# Maxim_7219_LED_display_KingBright_7_segm.net
KiCad netlist of a schematic drawn in EAGLE
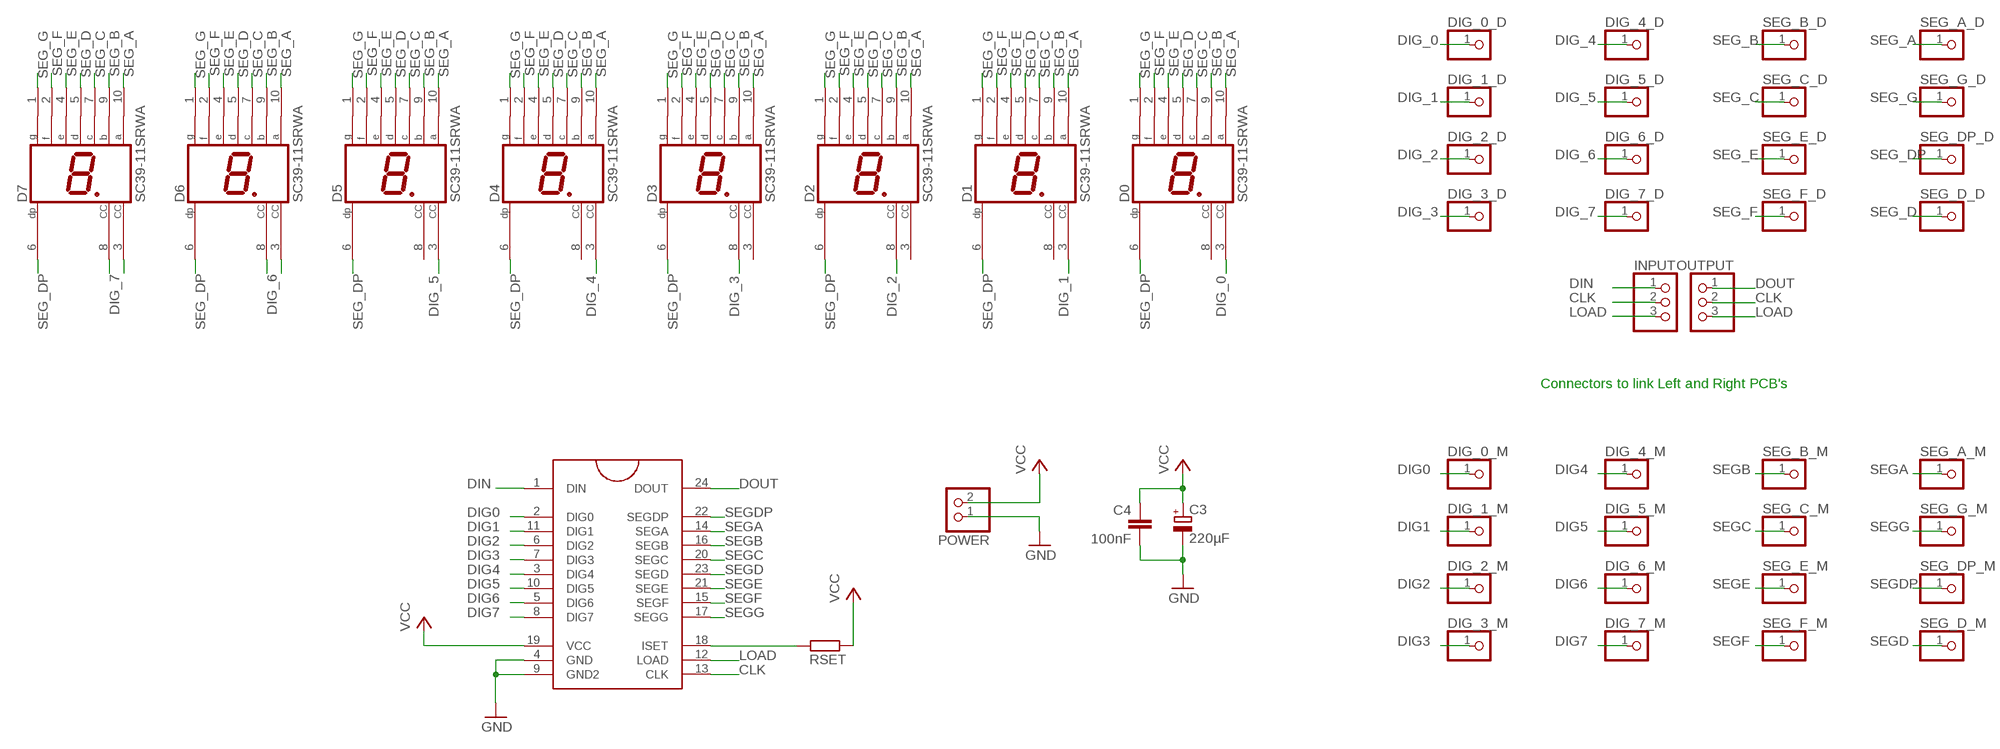
[diagram p0: schematic, sheet 1]

(export (version "E")
  (design (tool "Eeschema 10.0.6"))
  (components
    (comp (ref "C3")
      (value "220µF")
      (footprint "eagle-import:E3,5-8")
      (libsource (lib "eagle-import") (part "CPOL-EUE3.5-8"))
    )
    (comp (ref "C4")
      (value "100nF")
      (footprint "eagle-import:C050-025X075")
      (libsource (lib "eagle-import") (part "C-EU050-025X075"))
    )
    (comp (ref "D0")
      (value "SC39-11SRWA")
      (footprint "eagle-import:HDSP-E")
      (libsource (lib "eagle-import") (part "SC39-11SRWA"))
    )
    (comp (ref "D1")
      (value "SC39-11SRWA")
      (footprint "eagle-import:HDSP-E")
      (libsource (lib "eagle-import") (part "SC39-11SRWA"))
    )
    (comp (ref "D2")
      (value "SC39-11SRWA")
      (footprint "eagle-import:HDSP-E")
      (libsource (lib "eagle-import") (part "SC39-11SRWA"))
    )
    (comp (ref "D3")
      (value "SC39-11SRWA")
      (footprint "eagle-import:HDSP-E")
      (libsource (lib "eagle-import") (part "SC39-11SRWA"))
    )
    (comp (ref "D4")
      (value "SC39-11SRWA")
      (footprint "eagle-import:HDSP-E")
      (libsource (lib "eagle-import") (part "SC39-11SRWA"))
    )
    (comp (ref "D5")
      (value "SC39-11SRWA")
      (footprint "eagle-import:HDSP-E")
      (libsource (lib "eagle-import") (part "SC39-11SRWA"))
    )
    (comp (ref "D6")
      (value "SC39-11SRWA")
      (footprint "eagle-import:HDSP-E")
      (libsource (lib "eagle-import") (part "SC39-11SRWA"))
    )
    (comp (ref "D7")
      (value "SC39-11SRWA")
      (footprint "eagle-import:HDSP-E")
      (libsource (lib "eagle-import") (part "SC39-11SRWA"))
    )
    (comp (ref "DIG_0_D")
      (value "PINHD-1X1")
      (footprint "eagle-import:1X01")
      (libsource (lib "eagle-import") (part "PINHD-1X1"))
    )
    (comp (ref "DIG_0_M")
      (value "PINHD-1X1")
      (footprint "eagle-import:1X01")
      (libsource (lib "eagle-import") (part "PINHD-1X1"))
    )
    (comp (ref "DIG_1_D")
      (value "PINHD-1X1")
      (footprint "eagle-import:1X01")
      (libsource (lib "eagle-import") (part "PINHD-1X1"))
    )
    (comp (ref "DIG_1_M")
      (value "PINHD-1X1")
      (footprint "eagle-import:1X01")
      (libsource (lib "eagle-import") (part "PINHD-1X1"))
    )
    (comp (ref "DIG_2_D")
      (value "PINHD-1X1")
      (footprint "eagle-import:1X01")
      (libsource (lib "eagle-import") (part "PINHD-1X1"))
    )
    (comp (ref "DIG_2_M")
      (value "PINHD-1X1")
      (footprint "eagle-import:1X01")
      (libsource (lib "eagle-import") (part "PINHD-1X1"))
    )
    (comp (ref "DIG_3_D")
      (value "PINHD-1X1")
      (footprint "eagle-import:1X01")
      (libsource (lib "eagle-import") (part "PINHD-1X1"))
    )
    (comp (ref "DIG_3_M")
      (value "PINHD-1X1")
      (footprint "eagle-import:1X01")
      (libsource (lib "eagle-import") (part "PINHD-1X1"))
    )
    (comp (ref "DIG_4_D")
      (value "PINHD-1X1")
      (footprint "eagle-import:1X01")
      (libsource (lib "eagle-import") (part "PINHD-1X1"))
    )
    (comp (ref "DIG_4_M")
      (value "PINHD-1X1")
      (footprint "eagle-import:1X01")
      (libsource (lib "eagle-import") (part "PINHD-1X1"))
    )
    (comp (ref "DIG_5_D")
      (value "PINHD-1X1")
      (footprint "eagle-import:1X01")
      (libsource (lib "eagle-import") (part "PINHD-1X1"))
    )
    (comp (ref "DIG_5_M")
      (value "PINHD-1X1")
      (footprint "eagle-import:1X01")
      (libsource (lib "eagle-import") (part "PINHD-1X1"))
    )
    (comp (ref "DIG_6_D")
      (value "PINHD-1X1")
      (footprint "eagle-import:1X01")
      (libsource (lib "eagle-import") (part "PINHD-1X1"))
    )
    (comp (ref "DIG_6_M")
      (value "PINHD-1X1")
      (footprint "eagle-import:1X01")
      (libsource (lib "eagle-import") (part "PINHD-1X1"))
    )
    (comp (ref "DIG_7_D")
      (value "PINHD-1X1")
      (footprint "eagle-import:1X01")
      (libsource (lib "eagle-import") (part "PINHD-1X1"))
    )
    (comp (ref "DIG_7_M")
      (value "PINHD-1X1")
      (footprint "eagle-import:1X01")
      (libsource (lib "eagle-import") (part "PINHD-1X1"))
    )
    (comp (ref "INPUT")
      (value "PINHD-1X3")
      (footprint "eagle-import:1X03")
      (libsource (lib "eagle-import") (part "PINHD-1X3"))
    )
    (comp (ref "OUTPUT")
      (value "PINHD-1X3")
      (footprint "eagle-import:1X03")
      (libsource (lib "eagle-import") (part "PINHD-1X3"))
    )
    (comp (ref "POWER")
      (value "PINHD-1X2")
      (footprint "eagle-import:1X02")
      (libsource (lib "eagle-import") (part "PINHD-1X2"))
    )
    (comp (ref "RSET")
      (value "R-EU_0207/10")
      (footprint "eagle-import:0207_10")
      (libsource (lib "eagle-import") (part "R-EU_0207/10"))
    )
    (comp (ref "SEG_A_D")
      (value "PINHD-1X1")
      (footprint "eagle-import:1X01")
      (libsource (lib "eagle-import") (part "PINHD-1X1"))
    )
    (comp (ref "SEG_A_M")
      (value "PINHD-1X1")
      (footprint "eagle-import:1X01")
      (libsource (lib "eagle-import") (part "PINHD-1X1"))
    )
    (comp (ref "SEG_B_D")
      (value "PINHD-1X1")
      (footprint "eagle-import:1X01")
      (libsource (lib "eagle-import") (part "PINHD-1X1"))
    )
    (comp (ref "SEG_B_M")
      (value "PINHD-1X1")
      (footprint "eagle-import:1X01")
      (libsource (lib "eagle-import") (part "PINHD-1X1"))
    )
    (comp (ref "SEG_C_D")
      (value "PINHD-1X1")
      (footprint "eagle-import:1X01")
      (libsource (lib "eagle-import") (part "PINHD-1X1"))
    )
    (comp (ref "SEG_C_M")
      (value "PINHD-1X1")
      (footprint "eagle-import:1X01")
      (libsource (lib "eagle-import") (part "PINHD-1X1"))
    )
    (comp (ref "SEG_DP_D")
      (value "PINHD-1X1")
      (footprint "eagle-import:1X01")
      (libsource (lib "eagle-import") (part "PINHD-1X1"))
    )
    (comp (ref "SEG_DP_M")
      (value "PINHD-1X1")
      (footprint "eagle-import:1X01")
      (libsource (lib "eagle-import") (part "PINHD-1X1"))
    )
    (comp (ref "SEG_D_D")
      (value "PINHD-1X1")
      (footprint "eagle-import:1X01")
      (libsource (lib "eagle-import") (part "PINHD-1X1"))
    )
    (comp (ref "SEG_D_M")
      (value "PINHD-1X1")
      (footprint "eagle-import:1X01")
      (libsource (lib "eagle-import") (part "PINHD-1X1"))
    )
    (comp (ref "SEG_E_D")
      (value "PINHD-1X1")
      (footprint "eagle-import:1X01")
      (libsource (lib "eagle-import") (part "PINHD-1X1"))
    )
    (comp (ref "SEG_E_M")
      (value "PINHD-1X1")
      (footprint "eagle-import:1X01")
      (libsource (lib "eagle-import") (part "PINHD-1X1"))
    )
    (comp (ref "SEG_F_D")
      (value "PINHD-1X1")
      (footprint "eagle-import:1X01")
      (libsource (lib "eagle-import") (part "PINHD-1X1"))
    )
    (comp (ref "SEG_F_M")
      (value "PINHD-1X1")
      (footprint "eagle-import:1X01")
      (libsource (lib "eagle-import") (part "PINHD-1X1"))
    )
    (comp (ref "SEG_G_D")
      (value "PINHD-1X1")
      (footprint "eagle-import:1X01")
      (libsource (lib "eagle-import") (part "PINHD-1X1"))
    )
    (comp (ref "SEG_G_M")
      (value "PINHD-1X1")
      (footprint "eagle-import:1X01")
      (libsource (lib "eagle-import") (part "PINHD-1X1"))
    )
    (comp (ref "U$3")
      (value "MAX7219DIP")
      (footprint "eagle-import:DIL24")
      (libsource (lib "eagle-import") (part "MAX7219DIP"))
    )
  )
  (nets
    (net (code "1") (name "/CLK") (class "Default")
      (node (ref "INPUT") (pin "2") (pinfunction "2_2") (pintype "passive"))
      (node (ref "OUTPUT") (pin "2") (pinfunction "2_2") (pintype "passive"))
      (node (ref "U$3") (pin "13") (pinfunction "CLK_13") (pintype "bidirectional"))
    )
    (net (code "2") (name "/DIG0") (class "Default")
      (node (ref "DIG_0_M") (pin "1") (pinfunction "1_1") (pintype "passive"))
      (node (ref "U$3") (pin "2") (pinfunction "DIG0_2") (pintype "bidirectional"))
    )
    (net (code "3") (name "/DIG1") (class "Default")
      (node (ref "DIG_1_M") (pin "1") (pinfunction "1_1") (pintype "passive"))
      (node (ref "U$3") (pin "11") (pinfunction "DIG1_11") (pintype "bidirectional"))
    )
    (net (code "4") (name "/DIG2") (class "Default")
      (node (ref "DIG_2_M") (pin "1") (pinfunction "1_1") (pintype "passive"))
      (node (ref "U$3") (pin "6") (pinfunction "DIG2_6") (pintype "bidirectional"))
    )
    (net (code "5") (name "/DIG3") (class "Default")
      (node (ref "DIG_3_M") (pin "1") (pinfunction "1_1") (pintype "passive"))
      (node (ref "U$3") (pin "7") (pinfunction "DIG3_7") (pintype "bidirectional"))
    )
    (net (code "6") (name "/DIG4") (class "Default")
      (node (ref "DIG_4_M") (pin "1") (pinfunction "1_1") (pintype "passive"))
      (node (ref "U$3") (pin "3") (pinfunction "DIG4_3") (pintype "bidirectional"))
    )
    (net (code "7") (name "/DIG5") (class "Default")
      (node (ref "DIG_5_M") (pin "1") (pinfunction "1_1") (pintype "passive"))
      (node (ref "U$3") (pin "10") (pinfunction "DIG5_10") (pintype "bidirectional"))
    )
    (net (code "8") (name "/DIG6") (class "Default")
      (node (ref "DIG_6_M") (pin "1") (pinfunction "1_1") (pintype "passive"))
      (node (ref "U$3") (pin "5") (pinfunction "DIG6_5") (pintype "bidirectional"))
    )
    (net (code "9") (name "/DIG7") (class "Default")
      (node (ref "DIG_7_M") (pin "1") (pinfunction "1_1") (pintype "passive"))
      (node (ref "U$3") (pin "8") (pinfunction "DIG7_8") (pintype "bidirectional"))
    )
    (net (code "10") (name "/DIG_0") (class "Default")
      (node (ref "D0") (pin "3") (pinfunction "CC_3") (pintype "passive"))
      (node (ref "DIG_0_D") (pin "1") (pinfunction "1_1") (pintype "passive"))
    )
    (net (code "11") (name "/DIG_1") (class "Default")
      (node (ref "D1") (pin "3") (pinfunction "CC_3") (pintype "passive"))
      (node (ref "DIG_1_D") (pin "1") (pinfunction "1_1") (pintype "passive"))
    )
    (net (code "12") (name "/DIG_2") (class "Default")
      (node (ref "D2") (pin "8") (pinfunction "CC_8") (pintype "passive"))
      (node (ref "DIG_2_D") (pin "1") (pinfunction "1_1") (pintype "passive"))
    )
    (net (code "13") (name "/DIG_3") (class "Default")
      (node (ref "D3") (pin "8") (pinfunction "CC_8") (pintype "passive"))
      (node (ref "DIG_3_D") (pin "1") (pinfunction "1_1") (pintype "passive"))
    )
    (net (code "14") (name "/DIG_4") (class "Default")
      (node (ref "D4") (pin "3") (pinfunction "CC_3") (pintype "passive"))
      (node (ref "DIG_4_D") (pin "1") (pinfunction "1_1") (pintype "passive"))
    )
    (net (code "15") (name "/DIG_5") (class "Default")
      (node (ref "D5") (pin "3") (pinfunction "CC_3") (pintype "passive"))
      (node (ref "DIG_5_D") (pin "1") (pinfunction "1_1") (pintype "passive"))
    )
    (net (code "16") (name "/DIG_6") (class "Default")
      (node (ref "D6") (pin "8") (pinfunction "CC_8") (pintype "passive"))
      (node (ref "DIG_6_D") (pin "1") (pinfunction "1_1") (pintype "passive"))
    )
    (net (code "17") (name "/DIG_7") (class "Default")
      (node (ref "D7") (pin "8") (pinfunction "CC_8") (pintype "passive"))
      (node (ref "DIG_7_D") (pin "1") (pinfunction "1_1") (pintype "passive"))
    )
    (net (code "18") (name "/DIN") (class "Default")
      (node (ref "INPUT") (pin "1") (pinfunction "1_1") (pintype "passive"))
      (node (ref "U$3") (pin "1") (pinfunction "DIN_1") (pintype "bidirectional"))
    )
    (net (code "19") (name "/DOUT") (class "Default")
      (node (ref "OUTPUT") (pin "1") (pinfunction "1_1") (pintype "passive"))
      (node (ref "U$3") (pin "24") (pinfunction "DOUT_24") (pintype "bidirectional"))
    )
    (net (code "20") (name "/LOAD") (class "Default")
      (node (ref "INPUT") (pin "3") (pinfunction "3_3") (pintype "passive"))
      (node (ref "OUTPUT") (pin "3") (pinfunction "3_3") (pintype "passive"))
      (node (ref "U$3") (pin "12") (pinfunction "LOAD_12") (pintype "bidirectional"))
    )
    (net (code "21") (name "/SEGA") (class "Default")
      (node (ref "SEG_A_M") (pin "1") (pinfunction "1_1") (pintype "passive"))
      (node (ref "U$3") (pin "14") (pinfunction "SEGA_14") (pintype "bidirectional"))
    )
    (net (code "22") (name "/SEGB") (class "Default")
      (node (ref "SEG_B_M") (pin "1") (pinfunction "1_1") (pintype "passive"))
      (node (ref "U$3") (pin "16") (pinfunction "SEGB_16") (pintype "bidirectional"))
    )
    (net (code "23") (name "/SEGC") (class "Default")
      (node (ref "SEG_C_M") (pin "1") (pinfunction "1_1") (pintype "passive"))
      (node (ref "U$3") (pin "20") (pinfunction "SEGC_20") (pintype "bidirectional"))
    )
    (net (code "24") (name "/SEGD") (class "Default")
      (node (ref "SEG_D_M") (pin "1") (pinfunction "1_1") (pintype "passive"))
      (node (ref "U$3") (pin "23") (pinfunction "SEGD_23") (pintype "bidirectional"))
    )
    (net (code "25") (name "/SEGDP") (class "Default")
      (node (ref "SEG_DP_M") (pin "1") (pinfunction "1_1") (pintype "passive"))
      (node (ref "U$3") (pin "22") (pinfunction "SEGDP_22") (pintype "bidirectional"))
    )
    (net (code "26") (name "/SEGE") (class "Default")
      (node (ref "SEG_E_M") (pin "1") (pinfunction "1_1") (pintype "passive"))
      (node (ref "U$3") (pin "21") (pinfunction "SEGE_21") (pintype "bidirectional"))
    )
    (net (code "27") (name "/SEGF") (class "Default")
      (node (ref "SEG_F_M") (pin "1") (pinfunction "1_1") (pintype "passive"))
      (node (ref "U$3") (pin "15") (pinfunction "SEGF_15") (pintype "bidirectional"))
    )
    (net (code "28") (name "/SEGG") (class "Default")
      (node (ref "SEG_G_M") (pin "1") (pinfunction "1_1") (pintype "passive"))
      (node (ref "U$3") (pin "17") (pinfunction "SEGG_17") (pintype "bidirectional"))
    )
    (net (code "29") (name "/SEG_A") (class "Default")
      (node (ref "D0") (pin "10") (pinfunction "A_10") (pintype "passive"))
      (node (ref "D1") (pin "10") (pinfunction "A_10") (pintype "passive"))
      (node (ref "D2") (pin "10") (pinfunction "A_10") (pintype "passive"))
      (node (ref "D3") (pin "10") (pinfunction "A_10") (pintype "passive"))
      (node (ref "D4") (pin "10") (pinfunction "A_10") (pintype "passive"))
      (node (ref "D5") (pin "10") (pinfunction "A_10") (pintype "passive"))
      (node (ref "D6") (pin "10") (pinfunction "A_10") (pintype "passive"))
      (node (ref "D7") (pin "10") (pinfunction "A_10") (pintype "passive"))
      (node (ref "SEG_A_D") (pin "1") (pinfunction "1_1") (pintype "passive"))
    )
    (net (code "30") (name "/SEG_B") (class "Default")
      (node (ref "D0") (pin "9") (pinfunction "B_9") (pintype "passive"))
      (node (ref "D1") (pin "9") (pinfunction "B_9") (pintype "passive"))
      (node (ref "D2") (pin "9") (pinfunction "B_9") (pintype "passive"))
      (node (ref "D3") (pin "9") (pinfunction "B_9") (pintype "passive"))
      (node (ref "D4") (pin "9") (pinfunction "B_9") (pintype "passive"))
      (node (ref "D5") (pin "9") (pinfunction "B_9") (pintype "passive"))
      (node (ref "D6") (pin "9") (pinfunction "B_9") (pintype "passive"))
      (node (ref "D7") (pin "9") (pinfunction "B_9") (pintype "passive"))
      (node (ref "SEG_B_D") (pin "1") (pinfunction "1_1") (pintype "passive"))
    )
    (net (code "31") (name "/SEG_C") (class "Default")
      (node (ref "D0") (pin "7") (pinfunction "C_7") (pintype "passive"))
      (node (ref "D1") (pin "7") (pinfunction "C_7") (pintype "passive"))
      (node (ref "D2") (pin "7") (pinfunction "C_7") (pintype "passive"))
      (node (ref "D3") (pin "7") (pinfunction "C_7") (pintype "passive"))
      (node (ref "D4") (pin "7") (pinfunction "C_7") (pintype "passive"))
      (node (ref "D5") (pin "7") (pinfunction "C_7") (pintype "passive"))
      (node (ref "D6") (pin "7") (pinfunction "C_7") (pintype "passive"))
      (node (ref "D7") (pin "7") (pinfunction "C_7") (pintype "passive"))
      (node (ref "SEG_C_D") (pin "1") (pinfunction "1_1") (pintype "passive"))
    )
    (net (code "32") (name "/SEG_D") (class "Default")
      (node (ref "D0") (pin "5") (pinfunction "D_5") (pintype "passive"))
      (node (ref "D1") (pin "5") (pinfunction "D_5") (pintype "passive"))
      (node (ref "D2") (pin "5") (pinfunction "D_5") (pintype "passive"))
      (node (ref "D3") (pin "5") (pinfunction "D_5") (pintype "passive"))
      (node (ref "D4") (pin "5") (pinfunction "D_5") (pintype "passive"))
      (node (ref "D5") (pin "5") (pinfunction "D_5") (pintype "passive"))
      (node (ref "D6") (pin "5") (pinfunction "D_5") (pintype "passive"))
      (node (ref "D7") (pin "5") (pinfunction "D_5") (pintype "passive"))
      (node (ref "SEG_D_D") (pin "1") (pinfunction "1_1") (pintype "passive"))
    )
    (net (code "33") (name "/SEG_DP") (class "Default")
      (node (ref "D0") (pin "6") (pinfunction "DP_6") (pintype "passive"))
      (node (ref "D1") (pin "6") (pinfunction "DP_6") (pintype "passive"))
      (node (ref "D2") (pin "6") (pinfunction "DP_6") (pintype "passive"))
      (node (ref "D3") (pin "6") (pinfunction "DP_6") (pintype "passive"))
      (node (ref "D4") (pin "6") (pinfunction "DP_6") (pintype "passive"))
      (node (ref "D5") (pin "6") (pinfunction "DP_6") (pintype "passive"))
      (node (ref "D6") (pin "6") (pinfunction "DP_6") (pintype "passive"))
      (node (ref "D7") (pin "6") (pinfunction "DP_6") (pintype "passive"))
      (node (ref "SEG_DP_D") (pin "1") (pinfunction "1_1") (pintype "passive"))
    )
    (net (code "34") (name "/SEG_E") (class "Default")
      (node (ref "D0") (pin "4") (pinfunction "E_4") (pintype "passive"))
      (node (ref "D1") (pin "4") (pinfunction "E_4") (pintype "passive"))
      (node (ref "D2") (pin "4") (pinfunction "E_4") (pintype "passive"))
      (node (ref "D3") (pin "4") (pinfunction "E_4") (pintype "passive"))
      (node (ref "D4") (pin "4") (pinfunction "E_4") (pintype "passive"))
      (node (ref "D5") (pin "4") (pinfunction "E_4") (pintype "passive"))
      (node (ref "D6") (pin "4") (pinfunction "E_4") (pintype "passive"))
      (node (ref "D7") (pin "4") (pinfunction "E_4") (pintype "passive"))
      (node (ref "SEG_E_D") (pin "1") (pinfunction "1_1") (pintype "passive"))
    )
    (net (code "35") (name "/SEG_F") (class "Default")
      (node (ref "D0") (pin "2") (pinfunction "F_2") (pintype "passive"))
      (node (ref "D1") (pin "2") (pinfunction "F_2") (pintype "passive"))
      (node (ref "D2") (pin "2") (pinfunction "F_2") (pintype "passive"))
      (node (ref "D3") (pin "2") (pinfunction "F_2") (pintype "passive"))
      (node (ref "D4") (pin "2") (pinfunction "F_2") (pintype "passive"))
      (node (ref "D5") (pin "2") (pinfunction "F_2") (pintype "passive"))
      (node (ref "D6") (pin "2") (pinfunction "F_2") (pintype "passive"))
      (node (ref "D7") (pin "2") (pinfunction "F_2") (pintype "passive"))
      (node (ref "SEG_F_D") (pin "1") (pinfunction "1_1") (pintype "passive"))
    )
    (net (code "36") (name "/SEG_G") (class "Default")
      (node (ref "D0") (pin "1") (pinfunction "G_1") (pintype "passive"))
      (node (ref "D1") (pin "1") (pinfunction "G_1") (pintype "passive"))
      (node (ref "D2") (pin "1") (pinfunction "G_1") (pintype "passive"))
      (node (ref "D3") (pin "1") (pinfunction "G_1") (pintype "passive"))
      (node (ref "D4") (pin "1") (pinfunction "G_1") (pintype "passive"))
      (node (ref "D5") (pin "1") (pinfunction "G_1") (pintype "passive"))
      (node (ref "D6") (pin "1") (pinfunction "G_1") (pintype "passive"))
      (node (ref "D7") (pin "1") (pinfunction "G_1") (pintype "passive"))
      (node (ref "SEG_G_D") (pin "1") (pinfunction "1_1") (pintype "passive"))
    )
    (net (code "37") (name "GND") (class "Default")
      (node (ref "C3") (pin "-") (pinfunction "-_-") (pintype "passive"))
      (node (ref "C4") (pin "2") (pinfunction "2_2") (pintype "passive"))
      (node (ref "POWER") (pin "1") (pinfunction "1_1") (pintype "passive"))
      (node (ref "U$3") (pin "4") (pinfunction "GND_4") (pintype "bidirectional"))
      (node (ref "U$3") (pin "9") (pinfunction "GND2_9") (pintype "bidirectional"))
    )
    (net (code "38") (name "Net-(U$3-ISET)") (class "Default")
      (node (ref "RSET") (pin "2") (pinfunction "2_2") (pintype "passive"))
      (node (ref "U$3") (pin "18") (pinfunction "ISET_18") (pintype "bidirectional"))
    )
    (net (code "39") (name "VCC") (class "Default")
      (node (ref "C3") (pin "+") (pinfunction "+_+") (pintype "passive"))
      (node (ref "C4") (pin "1") (pinfunction "1_1") (pintype "passive"))
      (node (ref "POWER") (pin "2") (pinfunction "2_2") (pintype "passive"))
      (node (ref "RSET") (pin "1") (pinfunction "1_1") (pintype "passive"))
      (node (ref "U$3") (pin "19") (pinfunction "VCC_19") (pintype "bidirectional"))
    )
    (net (code "40") (name "unconnected-(D0-CC-Pad8)") (class "Default")
      (node (ref "D0") (pin "8") (pinfunction "CC_8") (pintype "passive"))
    )
    (net (code "41") (name "unconnected-(D1-CC-Pad8)") (class "Default")
      (node (ref "D1") (pin "8") (pinfunction "CC_8") (pintype "passive"))
    )
    (net (code "42") (name "unconnected-(D2-CC-Pad3)") (class "Default")
      (node (ref "D2") (pin "3") (pinfunction "CC_3") (pintype "passive"))
    )
    (net (code "43") (name "unconnected-(D3-CC-Pad3)") (class "Default")
      (node (ref "D3") (pin "3") (pinfunction "CC_3") (pintype "passive"))
    )
    (net (code "44") (name "unconnected-(D4-CC-Pad8)") (class "Default")
      (node (ref "D4") (pin "8") (pinfunction "CC_8") (pintype "passive"))
    )
    (net (code "45") (name "unconnected-(D5-CC-Pad8)") (class "Default")
      (node (ref "D5") (pin "8") (pinfunction "CC_8") (pintype "passive"))
    )
    (net (code "46") (name "unconnected-(D6-CC-Pad3)") (class "Default")
      (node (ref "D6") (pin "3") (pinfunction "CC_3") (pintype "passive"))
    )
    (net (code "47") (name "unconnected-(D7-CC-Pad3)") (class "Default")
      (node (ref "D7") (pin "3") (pinfunction "CC_3") (pintype "passive"))
    )
  )
)
